# board_pa98.net
KiCad netlist of a schematic drawn in Altium Designer
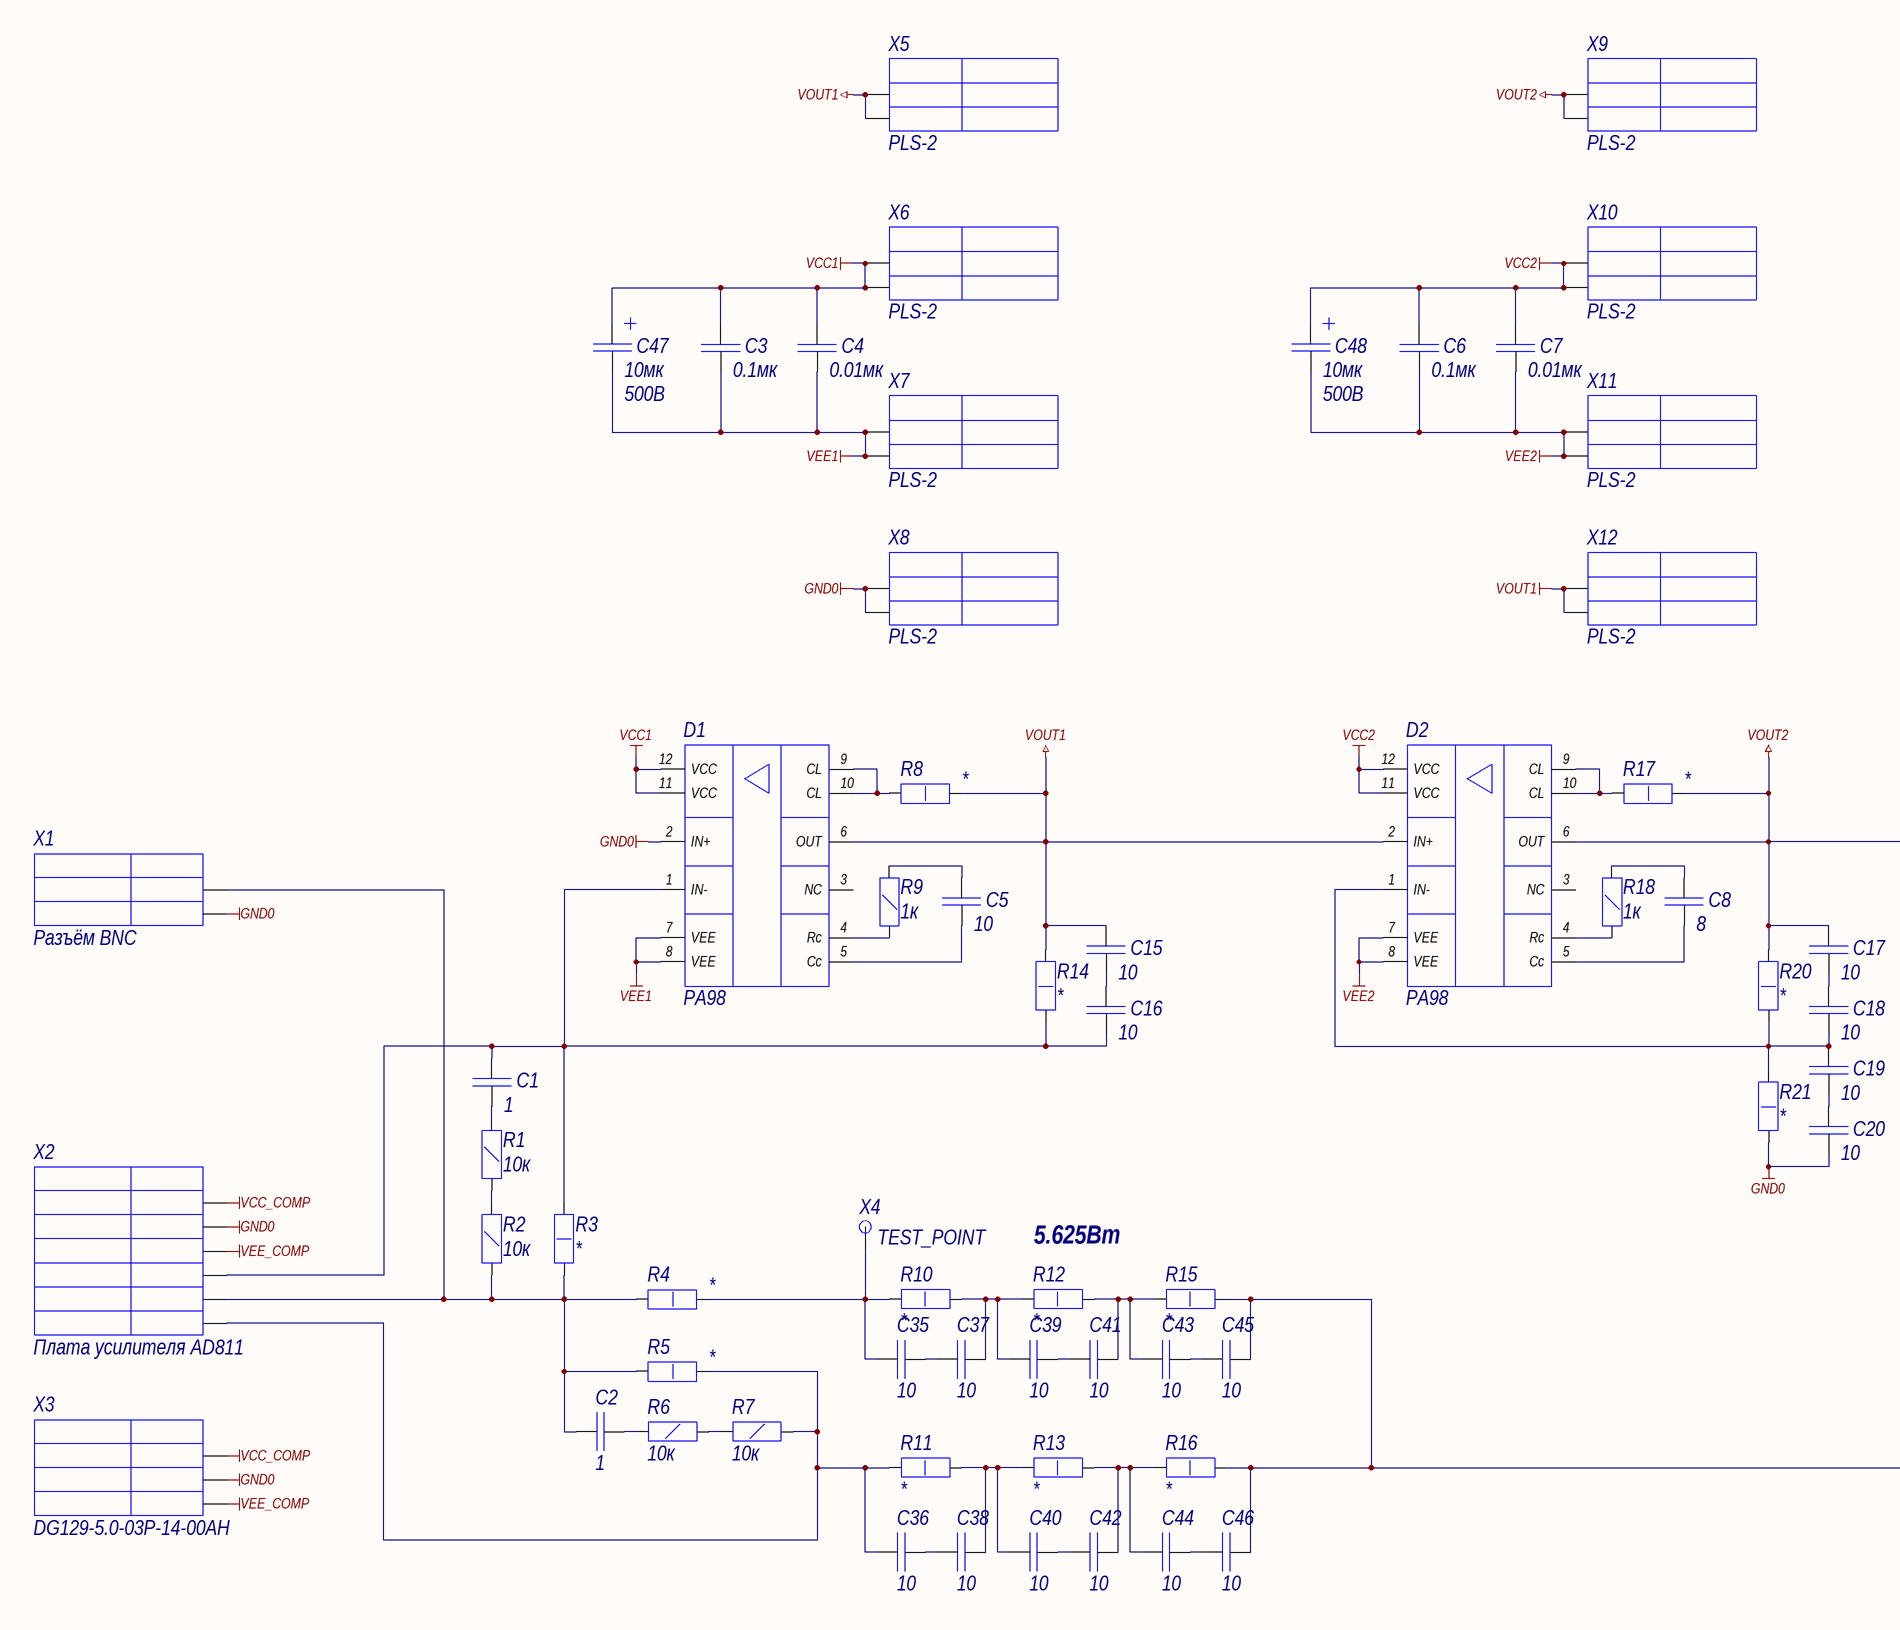
[diagram p0: board_pa98.SchDoc, left]
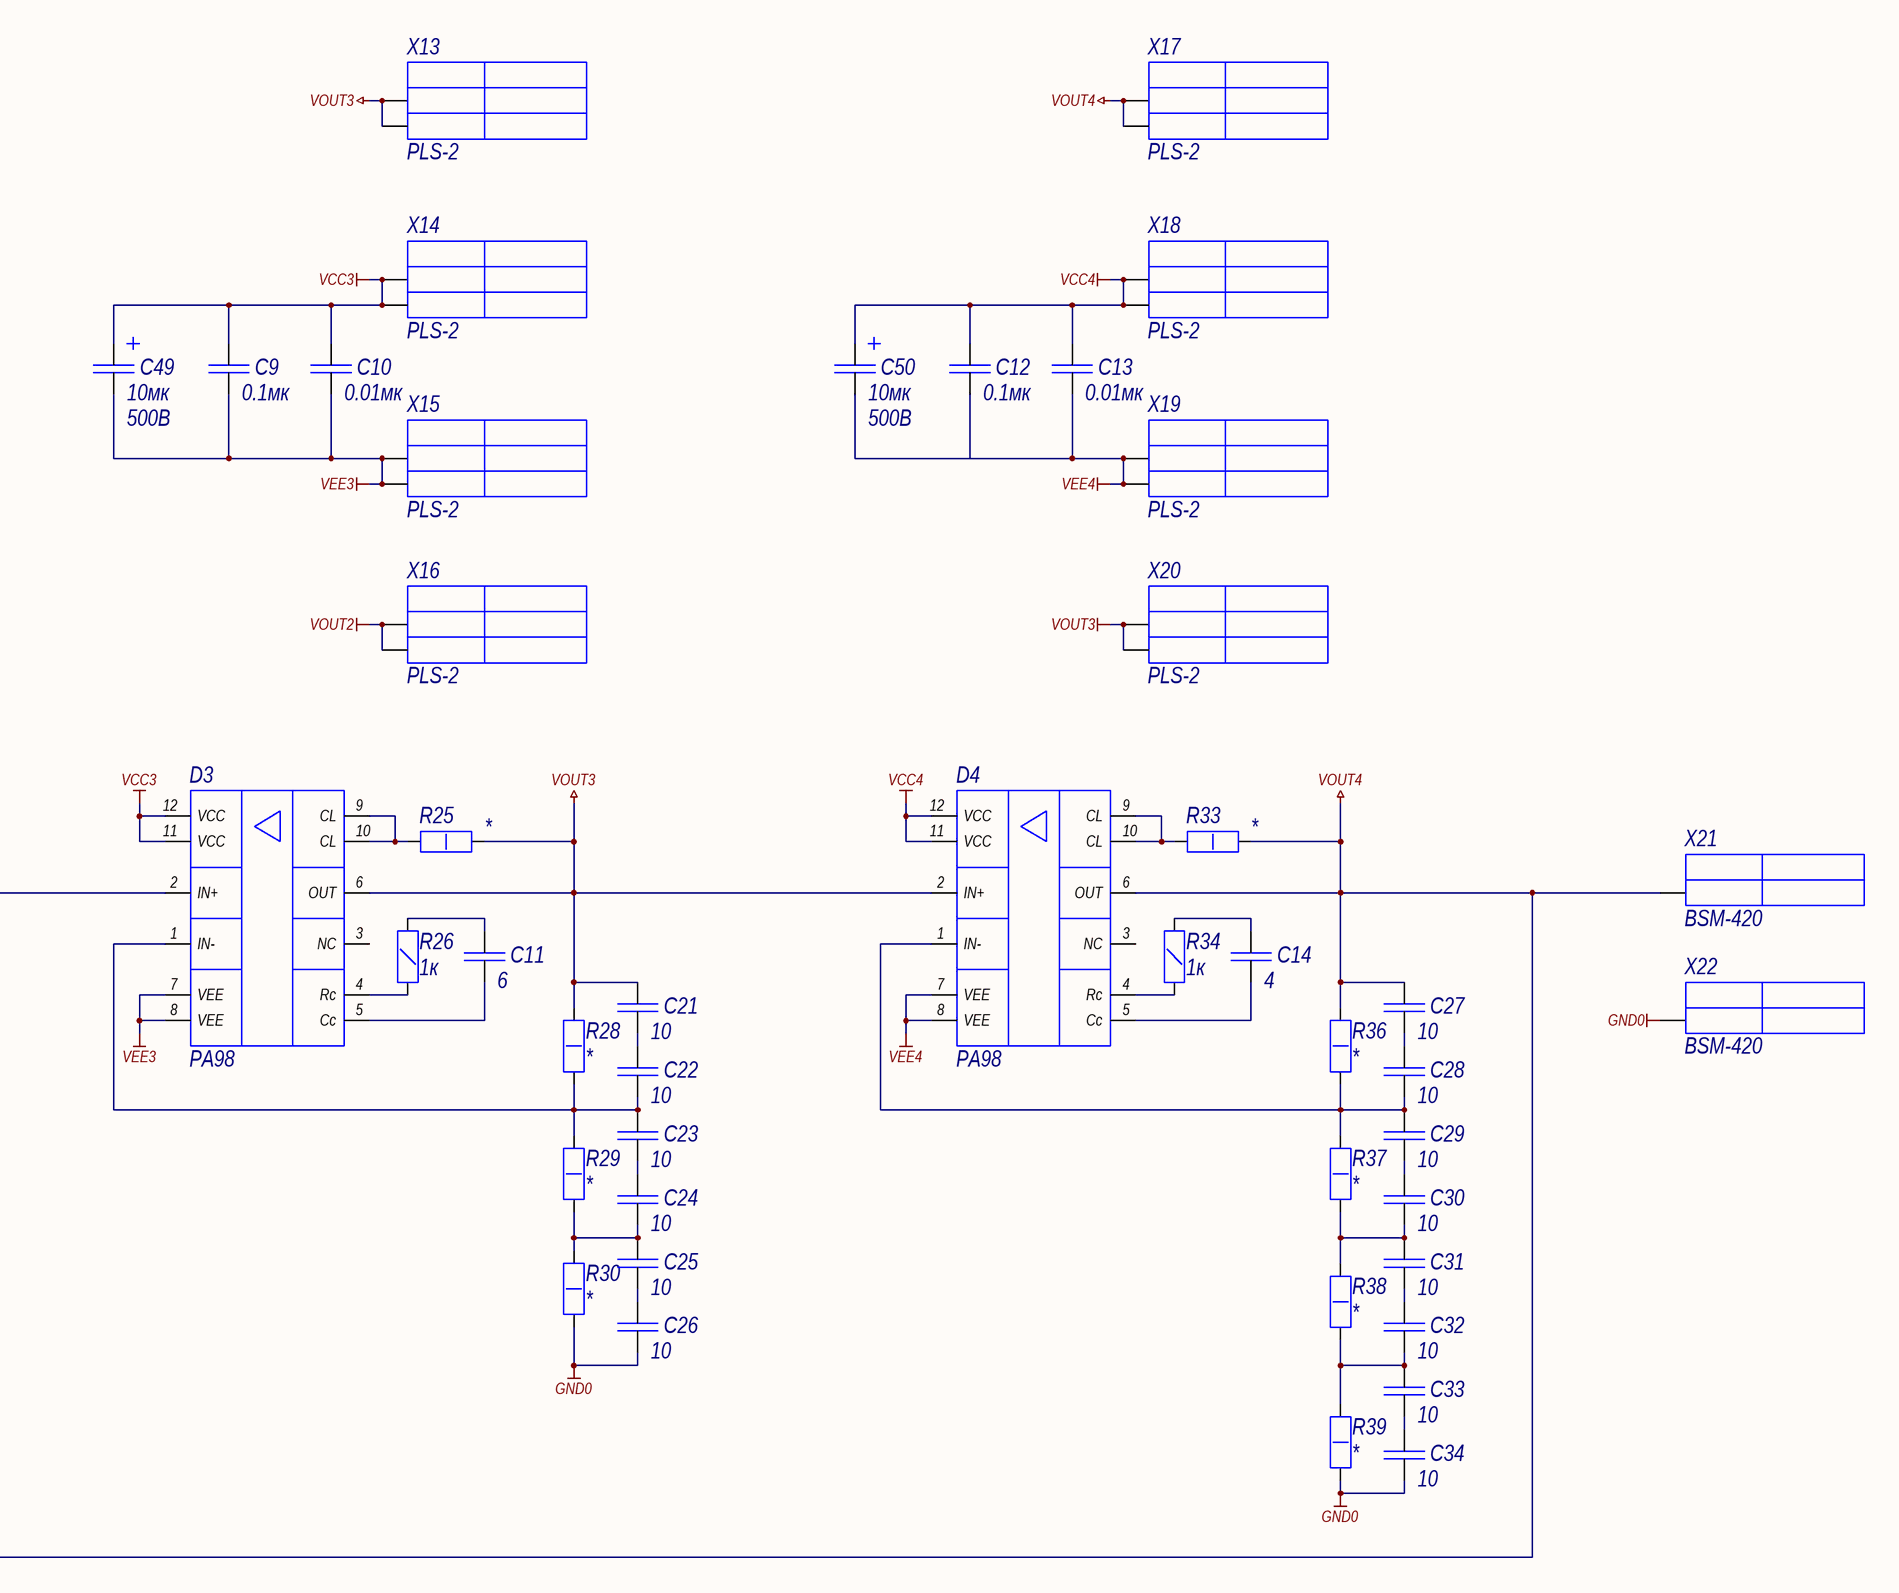
[diagram p1: board_pa98.SchDoc, right]

(export (version "E")
  (design (tool "Eeschema 10.0.6"))
  (components
    (comp (ref "C1")
      (value "1")
      (footprint "C-1206")
      (fields (field (name "VOLTAGE") "630В"))
      (libsource (lib "Capacitor") (part "C1206"))
    )
    (comp (ref "C2")
      (value "1")
      (footprint "C-1206")
      (fields (field (name "VOLTAGE") "630В"))
      (libsource (lib "Capacitor") (part "C1206"))
    )
    (comp (ref "C3")
      (value "0.1мк")
      (footprint "C-1812")
      (fields (field (name "VOLTAGE") "630"))
      (libsource (lib "Capacitor") (part "C1812"))
    )
    (comp (ref "C4")
      (value "0.01мк")
      (footprint "C-1206")
      (fields (field (name "VOLTAGE") "630"))
      (libsource (lib "Capacitor") (part "C1206"))
    )
    (comp (ref "C5")
      (value "10")
      (footprint "C-1206")
      (fields (field (name "VOLTAGE") "630В"))
      (libsource (lib "Capacitor") (part "C1206"))
    )
    (comp (ref "C6")
      (value "0.1мк")
      (footprint "C-1812")
      (fields (field (name "VOLTAGE") "630"))
      (libsource (lib "Capacitor") (part "C1812"))
    )
    (comp (ref "C7")
      (value "0.01мк")
      (footprint "C-1206")
      (fields (field (name "VOLTAGE") "630"))
      (libsource (lib "Capacitor") (part "C1206"))
    )
    (comp (ref "C8")
      (value "8")
      (footprint "C-1206")
      (fields (field (name "VOLTAGE") "630В"))
      (libsource (lib "Capacitor") (part "C1206"))
    )
    (comp (ref "C9")
      (value "0.1мк")
      (footprint "C-1812")
      (fields (field (name "VOLTAGE") "630"))
      (libsource (lib "Capacitor") (part "C1812"))
    )
    (comp (ref "C10")
      (value "0.01мк")
      (footprint "C-1206")
      (fields (field (name "VOLTAGE") "630"))
      (libsource (lib "Capacitor") (part "C1206"))
    )
    (comp (ref "C11")
      (value "6")
      (footprint "C-1206")
      (fields (field (name "VOLTAGE") "630В"))
      (libsource (lib "Capacitor") (part "C1206"))
    )
    (comp (ref "C12")
      (value "0.1мк")
      (footprint "C-1812")
      (fields (field (name "VOLTAGE") "630"))
      (libsource (lib "Capacitor") (part "C1812"))
    )
    (comp (ref "C13")
      (value "0.01мк")
      (footprint "C-1206")
      (fields (field (name "VOLTAGE") "630"))
      (libsource (lib "Capacitor") (part "C1206"))
    )
    (comp (ref "C14")
      (value "4")
      (footprint "C-1206")
      (fields (field (name "VOLTAGE") "630В"))
      (libsource (lib "Capacitor") (part "C1206"))
    )
    (comp (ref "C15")
      (value "10")
      (footprint "C-1206")
      (fields (field (name "VOLTAGE") "630В"))
      (libsource (lib "Capacitor") (part "C1206"))
    )
    (comp (ref "C16")
      (value "10")
      (footprint "C-1206")
      (fields (field (name "VOLTAGE") "630В"))
      (libsource (lib "Capacitor") (part "C1206"))
    )
    (comp (ref "C17")
      (value "10")
      (footprint "C-1206")
      (fields (field (name "VOLTAGE") "630В"))
      (libsource (lib "Capacitor") (part "C1206"))
    )
    (comp (ref "C18")
      (value "10")
      (footprint "C-1206")
      (fields (field (name "VOLTAGE") "630В"))
      (libsource (lib "Capacitor") (part "C1206"))
    )
    (comp (ref "C19")
      (value "10")
      (footprint "C-1206")
      (fields (field (name "VOLTAGE") "630В"))
      (libsource (lib "Capacitor") (part "C1206"))
    )
    (comp (ref "C20")
      (value "10")
      (footprint "C-1206")
      (fields (field (name "VOLTAGE") "630В"))
      (libsource (lib "Capacitor") (part "C1206"))
    )
    (comp (ref "C21")
      (value "10")
      (footprint "C-1206")
      (fields (field (name "VOLTAGE") "630В"))
      (libsource (lib "Capacitor") (part "C1206"))
    )
    (comp (ref "C22")
      (value "10")
      (footprint "C-1206")
      (fields (field (name "VOLTAGE") "630В"))
      (libsource (lib "Capacitor") (part "C1206"))
    )
    (comp (ref "C23")
      (value "10")
      (footprint "C-1206")
      (fields (field (name "VOLTAGE") "630В"))
      (libsource (lib "Capacitor") (part "C1206"))
    )
    (comp (ref "C24")
      (value "10")
      (footprint "C-1206")
      (fields (field (name "VOLTAGE") "630В"))
      (libsource (lib "Capacitor") (part "C1206"))
    )
    (comp (ref "C25")
      (value "10")
      (footprint "C-1206")
      (fields (field (name "VOLTAGE") "630В"))
      (libsource (lib "Capacitor") (part "C1206"))
    )
    (comp (ref "C26")
      (value "10")
      (footprint "C-1206")
      (fields (field (name "VOLTAGE") "630В"))
      (libsource (lib "Capacitor") (part "C1206"))
    )
    (comp (ref "C27")
      (value "10")
      (footprint "C-1206")
      (fields (field (name "VOLTAGE") "630В"))
      (libsource (lib "Capacitor") (part "C1206"))
    )
    (comp (ref "C28")
      (value "10")
      (footprint "C-1206")
      (fields (field (name "VOLTAGE") "630В"))
      (libsource (lib "Capacitor") (part "C1206"))
    )
    (comp (ref "C29")
      (value "10")
      (footprint "C-1206")
      (fields (field (name "VOLTAGE") "630В"))
      (libsource (lib "Capacitor") (part "C1206"))
    )
    (comp (ref "C30")
      (value "10")
      (footprint "C-1206")
      (fields (field (name "VOLTAGE") "630В"))
      (libsource (lib "Capacitor") (part "C1206"))
    )
    (comp (ref "C31")
      (value "10")
      (footprint "C-1206")
      (fields (field (name "VOLTAGE") "630В"))
      (libsource (lib "Capacitor") (part "C1206"))
    )
    (comp (ref "C32")
      (value "10")
      (footprint "C-1206")
      (fields (field (name "VOLTAGE") "630В"))
      (libsource (lib "Capacitor") (part "C1206"))
    )
    (comp (ref "C33")
      (value "10")
      (footprint "C-1206")
      (fields (field (name "VOLTAGE") "630В"))
      (libsource (lib "Capacitor") (part "C1206"))
    )
    (comp (ref "C34")
      (value "10")
      (footprint "C-1206")
      (fields (field (name "VOLTAGE") "630В"))
      (libsource (lib "Capacitor") (part "C1206"))
    )
    (comp (ref "C35")
      (value "10")
      (footprint "C-1206")
      (fields (field (name "VOLTAGE") "630В"))
      (libsource (lib "Capacitor") (part "C1206"))
    )
    (comp (ref "C36")
      (value "10")
      (footprint "C-1206")
      (fields (field (name "VOLTAGE") "630В"))
      (libsource (lib "Capacitor") (part "C1206"))
    )
    (comp (ref "C37")
      (value "10")
      (footprint "C-1206")
      (fields (field (name "VOLTAGE") "630В"))
      (libsource (lib "Capacitor") (part "C1206"))
    )
    (comp (ref "C38")
      (value "10")
      (footprint "C-1206")
      (fields (field (name "VOLTAGE") "630В"))
      (libsource (lib "Capacitor") (part "C1206"))
    )
    (comp (ref "C39")
      (value "10")
      (footprint "C-1206")
      (fields (field (name "VOLTAGE") "630В"))
      (libsource (lib "Capacitor") (part "C1206"))
    )
    (comp (ref "C40")
      (value "10")
      (footprint "C-1206")
      (fields (field (name "VOLTAGE") "630В"))
      (libsource (lib "Capacitor") (part "C1206"))
    )
    (comp (ref "C41")
      (value "10")
      (footprint "C-1206")
      (fields (field (name "VOLTAGE") "630В"))
      (libsource (lib "Capacitor") (part "C1206"))
    )
    (comp (ref "C42")
      (value "10")
      (footprint "C-1206")
      (fields (field (name "VOLTAGE") "630В"))
      (libsource (lib "Capacitor") (part "C1206"))
    )
    (comp (ref "C43")
      (value "10")
      (footprint "C-1206")
      (fields (field (name "VOLTAGE") "630В"))
      (libsource (lib "Capacitor") (part "C1206"))
    )
    (comp (ref "C44")
      (value "10")
      (footprint "C-1206")
      (fields (field (name "VOLTAGE") "630В"))
      (libsource (lib "Capacitor") (part "C1206"))
    )
    (comp (ref "C45")
      (value "10")
      (footprint "C-1206")
      (fields (field (name "VOLTAGE") "630В"))
      (libsource (lib "Capacitor") (part "C1206"))
    )
    (comp (ref "C46")
      (value "10")
      (footprint "C-1206")
      (fields (field (name "VOLTAGE") "630В"))
      (libsource (lib "Capacitor") (part "C1206"))
    )
    (comp (ref "C47")
      (value "10мк")
      (footprint "CAP: D13C5H25")
      (description "Конденсатор электролитический")
      (fields (field (name "VOLTAGE") "500В"))
      (libsource (lib "Capacitor") (part "Aluminum electrolytic capacitor"))
    )
    (comp (ref "C48")
      (value "10мк")
      (footprint "CAP: D13C5H25")
      (description "Конденсатор электролитический")
      (fields (field (name "VOLTAGE") "500В"))
      (libsource (lib "Capacitor") (part "Aluminum electrolytic capacitor"))
    )
    (comp (ref "C49")
      (value "10мк")
      (footprint "CAP: D13C5H25")
      (description "Конденсатор электролитический")
      (fields (field (name "VOLTAGE") "500В"))
      (libsource (lib "Capacitor") (part "Aluminum electrolytic capacitor"))
    )
    (comp (ref "C50")
      (value "10мк")
      (footprint "CAP: D13C5H25")
      (description "Конденсатор электролитический")
      (fields (field (name "VOLTAGE") "500В"))
      (libsource (lib "Capacitor") (part "Aluminum electrolytic capacitor"))
    )
    (comp (ref "D1")
      (value "PA98")
      (footprint "PA-98")
      (description "Микросхема  ОУ")
      (libsource (lib "IC_Operational_amp") (part "PA98"))
    )
    (comp (ref "D2")
      (value "PA98")
      (footprint "PA-98")
      (description "Микросхема  ОУ")
      (libsource (lib "IC_Operational_amp") (part "PA98"))
    )
    (comp (ref "D3")
      (value "PA98")
      (footprint "PA-98")
      (description "Микросхема  ОУ")
      (libsource (lib "IC_Operational_amp") (part "PA98"))
    )
    (comp (ref "D4")
      (value "PA98")
      (footprint "PA-98")
      (description "Микросхема  ОУ")
      (libsource (lib "IC_Operational_amp") (part "PA98"))
    )
    (comp (ref "R1")
      (value "10к")
      (footprint "R-1206")
      (description "Резистор SMD")
      (fields (field (name "TOLERANCE") "5%"))
      (libsource (lib "Resistor") (part "R1206"))
    )
    (comp (ref "R2")
      (value "10к")
      (footprint "R-1206")
      (description "Резистор SMD")
      (fields (field (name "TOLERANCE") "5%"))
      (libsource (lib "Resistor") (part "R1206"))
    )
    (comp (ref "R3")
      (value "*")
      (footprint "R-2512")
      (description "Резистор SMD")
      (fields (field (name "TOLERANCE") "5%"))
      (libsource (lib "Resistor") (part "R2512"))
    )
    (comp (ref "R4")
      (value "*")
      (footprint "R-2512")
      (description "Резистор SMD")
      (fields (field (name "TOLERANCE") "5%"))
      (libsource (lib "Resistor") (part "R2512"))
    )
    (comp (ref "R5")
      (value "*")
      (footprint "R-2512")
      (description "Резистор SMD")
      (fields (field (name "TOLERANCE") "5%"))
      (libsource (lib "Resistor") (part "R2512"))
    )
    (comp (ref "R6")
      (value "10к")
      (footprint "R-1206")
      (description "Резистор SMD")
      (fields (field (name "TOLERANCE") "5%"))
      (libsource (lib "Resistor") (part "R1206"))
    )
    (comp (ref "R7")
      (value "10к")
      (footprint "R-1206")
      (description "Резистор SMD")
      (fields (field (name "TOLERANCE") "5%"))
      (libsource (lib "Resistor") (part "R1206"))
    )
    (comp (ref "R8")
      (value "*")
      (footprint "R-2512")
      (description "Резистор SMD")
      (fields (field (name "TOLERANCE") "5%"))
      (libsource (lib "Resistor") (part "R2512"))
    )
    (comp (ref "R9")
      (value "1к")
      (footprint "R-1206")
      (description "Резистор SMD")
      (fields (field (name "TOLERANCE") "5%"))
      (libsource (lib "Resistor") (part "R1206"))
    )
    (comp (ref "R10")
      (value "*")
      (footprint "R-2512")
      (description "Резистор SMD")
      (fields (field (name "TOLERANCE") "5%"))
      (libsource (lib "Resistor") (part "R2512"))
    )
    (comp (ref "R11")
      (value "*")
      (footprint "R-2512")
      (description "Резистор SMD")
      (fields (field (name "TOLERANCE") "5%"))
      (libsource (lib "Resistor") (part "R2512"))
    )
    (comp (ref "R12")
      (value "*")
      (footprint "R-2512")
      (description "Резистор SMD")
      (fields (field (name "TOLERANCE") "5%"))
      (libsource (lib "Resistor") (part "R2512"))
    )
    (comp (ref "R13")
      (value "*")
      (footprint "R-2512")
      (description "Резистор SMD")
      (fields (field (name "TOLERANCE") "5%"))
      (libsource (lib "Resistor") (part "R2512"))
    )
    (comp (ref "R14")
      (value "*")
      (footprint "R-2512")
      (description "Резистор SMD")
      (fields (field (name "TOLERANCE") "5%"))
      (libsource (lib "Resistor") (part "R2512"))
    )
    (comp (ref "R15")
      (value "*")
      (footprint "R-2512")
      (description "Резистор SMD")
      (fields (field (name "TOLERANCE") "5%"))
      (libsource (lib "Resistor") (part "R2512"))
    )
    (comp (ref "R16")
      (value "*")
      (footprint "R-2512")
      (description "Резистор SMD")
      (fields (field (name "TOLERANCE") "5%"))
      (libsource (lib "Resistor") (part "R2512"))
    )
    (comp (ref "R17")
      (value "*")
      (footprint "R-2512")
      (description "Резистор SMD")
      (fields (field (name "TOLERANCE") "5%"))
      (libsource (lib "Resistor") (part "R2512"))
    )
    (comp (ref "R18")
      (value "1к")
      (footprint "R-1206")
      (description "Резистор SMD")
      (fields (field (name "TOLERANCE") "5%"))
      (libsource (lib "Resistor") (part "R1206"))
    )
    (comp (ref "R20")
      (value "*")
      (footprint "R-2512")
      (description "Резистор SMD")
      (fields (field (name "TOLERANCE") "5%"))
      (libsource (lib "Resistor") (part "R2512"))
    )
    (comp (ref "R21")
      (value "*")
      (footprint "R-2512")
      (description "Резистор SMD")
      (fields (field (name "TOLERANCE") "5%"))
      (libsource (lib "Resistor") (part "R2512"))
    )
    (comp (ref "R25")
      (value "*")
      (footprint "R-2512")
      (description "Резистор SMD")
      (fields (field (name "TOLERANCE") "5%"))
      (libsource (lib "Resistor") (part "R2512"))
    )
    (comp (ref "R26")
      (value "1к")
      (footprint "R-1206")
      (description "Резистор SMD")
      (fields (field (name "TOLERANCE") "5%"))
      (libsource (lib "Resistor") (part "R1206"))
    )
    (comp (ref "R28")
      (value "*")
      (footprint "R-2512")
      (description "Резистор SMD")
      (fields (field (name "TOLERANCE") "5%"))
      (libsource (lib "Resistor") (part "R2512"))
    )
    (comp (ref "R29")
      (value "*")
      (footprint "R-2512")
      (description "Резистор SMD")
      (fields (field (name "TOLERANCE") "5%"))
      (libsource (lib "Resistor") (part "R2512"))
    )
    (comp (ref "R30")
      (value "*")
      (footprint "R-2512")
      (description "Резистор SMD")
      (fields (field (name "TOLERANCE") "5%"))
      (libsource (lib "Resistor") (part "R2512"))
    )
    (comp (ref "R33")
      (value "*")
      (footprint "R-2512")
      (description "Резистор SMD")
      (fields (field (name "TOLERANCE") "5%"))
      (libsource (lib "Resistor") (part "R2512"))
    )
    (comp (ref "R34")
      (value "1к")
      (footprint "R-1206")
      (description "Резистор SMD")
      (fields (field (name "TOLERANCE") "5%"))
      (libsource (lib "Resistor") (part "R1206"))
    )
    (comp (ref "R36")
      (value "*")
      (footprint "R-2512")
      (description "Резистор SMD")
      (fields (field (name "TOLERANCE") "5%"))
      (libsource (lib "Resistor") (part "R2512"))
    )
    (comp (ref "R37")
      (value "*")
      (footprint "R-2512")
      (description "Резистор SMD")
      (fields (field (name "TOLERANCE") "5%"))
      (libsource (lib "Resistor") (part "R2512"))
    )
    (comp (ref "R38")
      (value "*")
      (footprint "R-2512")
      (description "Резистор SMD")
      (fields (field (name "TOLERANCE") "5%"))
      (libsource (lib "Resistor") (part "R2512"))
    )
    (comp (ref "R39")
      (value "*")
      (footprint "R-2512")
      (description "Резистор SMD")
      (fields (field (name "TOLERANCE") "5%"))
      (libsource (lib "Resistor") (part "R2512"))
    )
    (comp (ref "X1")
      (value "Разъём BNC")
      (footprint "BNC")
      (description "Разъём")
      (fields (field (name "PARTNUMBER") "32K249-400L5"))
      (libsource (lib "CONNECTORS") (part "BNC"))
    )
    (comp (ref "X2")
      (value "Плата усилителя AD811")
      (footprint "BOARD_AD811")
      (libsource (lib "BOARDS") (part "BOARD_AD811"))
    )
    (comp (ref "X3")
      (value "DG129-5.0-03P-14-00AH")
      (footprint "DG129-5.0-03P-14-00AH")
      (description "Разъем винтовой")
      (libsource (lib "CONNECTORS") (part "DG129-5.0-03P-14-00AH"))
    )
    (comp (ref "X4")
      (value "TEST_POINT")
      (footprint "TEST_POINT")
      (description "Тестовый контакт")
      (libsource (lib "CONNECTORS") (part "TEST_POINT"))
    )
    (comp (ref "X5")
      (value "PLS-2")
      (footprint "PLS-2")
      (description "Разъём штыревой")
      (libsource (lib "CONNECTORS") (part "PLS-2"))
    )
    (comp (ref "X6")
      (value "PLS-2")
      (footprint "PLS-2")
      (description "Разъём штыревой")
      (libsource (lib "CONNECTORS") (part "PLS-2"))
    )
    (comp (ref "X7")
      (value "PLS-2")
      (footprint "PLS-2")
      (description "Разъём штыревой")
      (libsource (lib "CONNECTORS") (part "PLS-2"))
    )
    (comp (ref "X8")
      (value "PLS-2")
      (footprint "PLS-2")
      (description "Разъём штыревой")
      (libsource (lib "CONNECTORS") (part "PLS-2"))
    )
    (comp (ref "X9")
      (value "PLS-2")
      (footprint "PLS-2")
      (description "Разъём штыревой")
      (libsource (lib "CONNECTORS") (part "PLS-2"))
    )
    (comp (ref "X10")
      (value "PLS-2")
      (footprint "PLS-2")
      (description "Разъём штыревой")
      (libsource (lib "CONNECTORS") (part "PLS-2"))
    )
    (comp (ref "X11")
      (value "PLS-2")
      (footprint "PLS-2")
      (description "Разъём штыревой")
      (libsource (lib "CONNECTORS") (part "PLS-2"))
    )
    (comp (ref "X12")
      (value "PLS-2")
      (footprint "PLS-2")
      (description "Разъём штыревой")
      (libsource (lib "CONNECTORS") (part "PLS-2"))
    )
    (comp (ref "X13")
      (value "PLS-2")
      (footprint "PLS-2")
      (description "Разъём штыревой")
      (libsource (lib "CONNECTORS") (part "PLS-2"))
    )
    (comp (ref "X14")
      (value "PLS-2")
      (footprint "PLS-2")
      (description "Разъём штыревой")
      (libsource (lib "CONNECTORS") (part "PLS-2"))
    )
    (comp (ref "X15")
      (value "PLS-2")
      (footprint "PLS-2")
      (description "Разъём штыревой")
      (libsource (lib "CONNECTORS") (part "PLS-2"))
    )
    (comp (ref "X16")
      (value "PLS-2")
      (footprint "PLS-2")
      (description "Разъём штыревой")
      (libsource (lib "CONNECTORS") (part "PLS-2"))
    )
    (comp (ref "X17")
      (value "PLS-2")
      (footprint "PLS-2")
      (description "Разъём штыревой")
      (libsource (lib "CONNECTORS") (part "PLS-2"))
    )
    (comp (ref "X18")
      (value "PLS-2")
      (footprint "PLS-2")
      (description "Разъём штыревой")
      (libsource (lib "CONNECTORS") (part "PLS-2"))
    )
    (comp (ref "X19")
      (value "PLS-2")
      (footprint "PLS-2")
      (description "Разъём штыревой")
      (libsource (lib "CONNECTORS") (part "PLS-2"))
    )
    (comp (ref "X20")
      (value "PLS-2")
      (footprint "PLS-2")
      (description "Разъём штыревой")
      (libsource (lib "CONNECTORS") (part "PLS-2"))
    )
    (comp (ref "X21")
      (value "BSM-420")
      (footprint "BSM-420-R")
      (description "Разъём")
      (fields (field (name "PARTNUMBER") "32K249-400L5"))
      (libsource (lib "CONNECTORS") (part "BSM-420"))
    )
    (comp (ref "X22")
      (value "BSM-420")
      (footprint "BSM-420-B")
      (description "Разъём")
      (fields (field (name "PARTNUMBER") "32K249-400L5"))
      (libsource (lib "CONNECTORS") (part "BSM-420"))
    )
  )
  (nets
    (net (code "1") (name "GND0") (class "Default")
      (node (ref "C20") (pin "2") (pintype "passive"))
      (node (ref "C26") (pin "2") (pintype "passive"))
      (node (ref "C34") (pin "2") (pintype "passive"))
      (node (ref "D1") (pin "2") (pinfunction "IN+_2") (pintype "passive"))
      (node (ref "R21") (pin "1") (pintype "passive"))
      (node (ref "R30") (pin "1") (pintype "passive"))
      (node (ref "R39") (pin "1") (pintype "passive"))
      (node (ref "X1") (pin "2") (pintype "passive"))
      (node (ref "X2") (pin "2") (pintype "passive"))
      (node (ref "X22") (pin "1") (pintype "passive"))
      (node (ref "X3") (pin "2") (pintype "passive"))
      (node (ref "X8") (pin "1") (pintype "passive"))
      (node (ref "X8") (pin "2") (pintype "passive"))
    )
    (net (code "2") (name "Net-(C1-Pad2)") (class "Default")
      (node (ref "C1") (pin "2") (pintype "passive"))
      (node (ref "R1") (pin "2") (pintype "passive"))
    )
    (net (code "3") (name "Net-(C2-Pad1)") (class "Default")
      (node (ref "C2") (pin "1") (pintype "passive"))
      (node (ref "R2") (pin "1") (pintype "passive"))
      (node (ref "R3") (pin "1") (pintype "passive"))
      (node (ref "R4") (pin "1") (pintype "passive"))
      (node (ref "R5") (pin "1") (pintype "passive"))
      (node (ref "X1") (pin "1") (pintype "passive"))
      (node (ref "X2") (pin "5") (pintype "passive"))
    )
    (net (code "4") (name "Net-(C2-Pad2)") (class "Default")
      (node (ref "C2") (pin "2") (pintype "passive"))
      (node (ref "R6") (pin "2") (pintype "passive"))
    )
    (net (code "5") (name "Net-(C5-Pad1)") (class "Default")
      (node (ref "C5") (pin "1") (pintype "passive"))
      (node (ref "R9") (pin "1") (pintype "passive"))
    )
    (net (code "6") (name "Net-(C8-Pad1)") (class "Default")
      (node (ref "C8") (pin "1") (pintype "passive"))
      (node (ref "R18") (pin "1") (pintype "passive"))
    )
    (net (code "7") (name "Net-(C11-Pad1)") (class "Default")
      (node (ref "C11") (pin "1") (pintype "passive"))
      (node (ref "R26") (pin "1") (pintype "passive"))
    )
    (net (code "8") (name "Net-(C14-Pad1)") (class "Default")
      (node (ref "C14") (pin "1") (pintype "passive"))
      (node (ref "R34") (pin "1") (pintype "passive"))
    )
    (net (code "9") (name "Net-(C15-Pad2)") (class "Default")
      (node (ref "C15") (pin "2") (pintype "passive"))
      (node (ref "C16") (pin "1") (pintype "passive"))
    )
    (net (code "10") (name "Net-(C17-Pad2)") (class "Default")
      (node (ref "C17") (pin "2") (pintype "passive"))
      (node (ref "C18") (pin "1") (pintype "passive"))
    )
    (net (code "11") (name "Net-(C19-Pad2)") (class "Default")
      (node (ref "C19") (pin "2") (pintype "passive"))
      (node (ref "C20") (pin "1") (pintype "passive"))
    )
    (net (code "12") (name "Net-(C21-Pad2)") (class "Default")
      (node (ref "C21") (pin "2") (pintype "passive"))
      (node (ref "C22") (pin "1") (pintype "passive"))
    )
    (net (code "13") (name "Net-(C23-Pad2)") (class "Default")
      (node (ref "C23") (pin "2") (pintype "passive"))
      (node (ref "C24") (pin "1") (pintype "passive"))
    )
    (net (code "14") (name "Net-(C24-Pad2)") (class "Default")
      (node (ref "C24") (pin "2") (pintype "passive"))
      (node (ref "C25") (pin "1") (pintype "passive"))
      (node (ref "R29") (pin "1") (pintype "passive"))
      (node (ref "R30") (pin "2") (pintype "passive"))
    )
    (net (code "15") (name "Net-(C25-Pad2)") (class "Default")
      (node (ref "C25") (pin "2") (pintype "passive"))
      (node (ref "C26") (pin "1") (pintype "passive"))
    )
    (net (code "16") (name "Net-(C27-Pad2)") (class "Default")
      (node (ref "C27") (pin "2") (pintype "passive"))
      (node (ref "C28") (pin "1") (pintype "passive"))
    )
    (net (code "17") (name "Net-(C29-Pad2)") (class "Default")
      (node (ref "C29") (pin "2") (pintype "passive"))
      (node (ref "C30") (pin "1") (pintype "passive"))
    )
    (net (code "18") (name "Net-(C30-Pad2)") (class "Default")
      (node (ref "C30") (pin "2") (pintype "passive"))
      (node (ref "C31") (pin "1") (pintype "passive"))
      (node (ref "R37") (pin "1") (pintype "passive"))
      (node (ref "R38") (pin "2") (pintype "passive"))
    )
    (net (code "19") (name "Net-(C31-Pad2)") (class "Default")
      (node (ref "C31") (pin "2") (pintype "passive"))
      (node (ref "C32") (pin "1") (pintype "passive"))
    )
    (net (code "20") (name "Net-(C32-Pad2)") (class "Default")
      (node (ref "C32") (pin "2") (pintype "passive"))
      (node (ref "C33") (pin "1") (pintype "passive"))
      (node (ref "R38") (pin "1") (pintype "passive"))
      (node (ref "R39") (pin "2") (pintype "passive"))
    )
    (net (code "21") (name "Net-(C33-Pad2)") (class "Default")
      (node (ref "C33") (pin "2") (pintype "passive"))
      (node (ref "C34") (pin "1") (pintype "passive"))
    )
    (net (code "22") (name "Net-(C35-Pad1)") (class "Default")
      (node (ref "C35") (pin "1") (pintype "passive"))
      (node (ref "C37") (pin "2") (pintype "passive"))
    )
    (net (code "23") (name "Net-(C35-Pad2)") (class "Default")
      (node (ref "C35") (pin "2") (pintype "passive"))
      (node (ref "R10") (pin "2") (pintype "passive"))
      (node (ref "R4") (pin "2") (pintype "passive"))
      (node (ref "X4") (pin "1") (pinfunction "1_1") (pintype "passive"))
    )
    (net (code "24") (name "Net-(C36-Pad1)") (class "Default")
      (node (ref "C36") (pin "1") (pintype "passive"))
      (node (ref "C38") (pin "2") (pintype "passive"))
    )
    (net (code "25") (name "Net-(C36-Pad2)") (class "Default")
      (node (ref "C36") (pin "2") (pintype "passive"))
      (node (ref "R11") (pin "2") (pintype "passive"))
      (node (ref "R5") (pin "2") (pintype "passive"))
      (node (ref "R7") (pin "1") (pintype "passive"))
      (node (ref "X2") (pin "6") (pintype "passive"))
    )
    (net (code "26") (name "Net-(C37-Pad1)") (class "Default")
      (node (ref "C37") (pin "1") (pintype "passive"))
      (node (ref "C39") (pin "2") (pintype "passive"))
      (node (ref "R10") (pin "1") (pintype "passive"))
      (node (ref "R12") (pin "2") (pintype "passive"))
    )
    (net (code "27") (name "Net-(C38-Pad1)") (class "Default")
      (node (ref "C38") (pin "1") (pintype "passive"))
      (node (ref "C40") (pin "2") (pintype "passive"))
      (node (ref "R11") (pin "1") (pintype "passive"))
      (node (ref "R13") (pin "2") (pintype "passive"))
    )
    (net (code "28") (name "Net-(C39-Pad1)") (class "Default")
      (node (ref "C39") (pin "1") (pintype "passive"))
      (node (ref "C41") (pin "2") (pintype "passive"))
    )
    (net (code "29") (name "Net-(C40-Pad1)") (class "Default")
      (node (ref "C40") (pin "1") (pintype "passive"))
      (node (ref "C42") (pin "2") (pintype "passive"))
    )
    (net (code "30") (name "Net-(C41-Pad1)") (class "Default")
      (node (ref "C41") (pin "1") (pintype "passive"))
      (node (ref "C43") (pin "2") (pintype "passive"))
      (node (ref "R12") (pin "1") (pintype "passive"))
      (node (ref "R15") (pin "2") (pintype "passive"))
    )
    (net (code "31") (name "Net-(C42-Pad1)") (class "Default")
      (node (ref "C42") (pin "1") (pintype "passive"))
      (node (ref "C44") (pin "2") (pintype "passive"))
      (node (ref "R13") (pin "1") (pintype "passive"))
      (node (ref "R16") (pin "2") (pintype "passive"))
    )
    (net (code "32") (name "Net-(C43-Pad1)") (class "Default")
      (node (ref "C43") (pin "1") (pintype "passive"))
      (node (ref "C45") (pin "2") (pintype "passive"))
    )
    (net (code "33") (name "Net-(C44-Pad1)") (class "Default")
      (node (ref "C44") (pin "1") (pintype "passive"))
      (node (ref "C46") (pin "2") (pintype "passive"))
    )
    (net (code "34") (name "Net-(D1-CL-Pad10)") (class "Default")
      (node (ref "D1") (pin "10") (pinfunction "CL_10") (pintype "passive"))
      (node (ref "D1") (pin "9") (pinfunction "CL_9") (pintype "passive"))
      (node (ref "R8") (pin "1") (pintype "passive"))
    )
    (net (code "35") (name "Net-(D1-Cc)") (class "Default")
      (node (ref "C5") (pin "2") (pintype "passive"))
      (node (ref "D1") (pin "5") (pinfunction "Cc_5") (pintype "passive"))
    )
    (net (code "36") (name "Net-(D1-IN-)") (class "Default")
      (node (ref "C1") (pin "1") (pintype "passive"))
      (node (ref "C16") (pin "2") (pintype "passive"))
      (node (ref "D1") (pin "1") (pinfunction "IN-_1") (pintype "passive"))
      (node (ref "R14") (pin "1") (pintype "passive"))
      (node (ref "R3") (pin "2") (pintype "passive"))
      (node (ref "X2") (pin "4") (pintype "passive"))
    )
    (net (code "37") (name "Net-(D1-Rc)") (class "Default")
      (node (ref "D1") (pin "4") (pinfunction "Rc_4") (pintype "passive"))
      (node (ref "R9") (pin "2") (pintype "passive"))
    )
    (net (code "38") (name "Net-(D2-CL-Pad10)") (class "Default")
      (node (ref "D2") (pin "10") (pinfunction "CL_10") (pintype "passive"))
      (node (ref "D2") (pin "9") (pinfunction "CL_9") (pintype "passive"))
      (node (ref "R17") (pin "1") (pintype "passive"))
    )
    (net (code "39") (name "Net-(D2-Cc)") (class "Default")
      (node (ref "C8") (pin "2") (pintype "passive"))
      (node (ref "D2") (pin "5") (pinfunction "Cc_5") (pintype "passive"))
    )
    (net (code "40") (name "Net-(D2-IN-)") (class "Default")
      (node (ref "C18") (pin "2") (pintype "passive"))
      (node (ref "C19") (pin "1") (pintype "passive"))
      (node (ref "D2") (pin "1") (pinfunction "IN-_1") (pintype "passive"))
      (node (ref "R20") (pin "1") (pintype "passive"))
      (node (ref "R21") (pin "2") (pintype "passive"))
    )
    (net (code "41") (name "Net-(D2-Rc)") (class "Default")
      (node (ref "D2") (pin "4") (pinfunction "Rc_4") (pintype "passive"))
      (node (ref "R18") (pin "2") (pintype "passive"))
    )
    (net (code "42") (name "Net-(D3-CL-Pad10)") (class "Default")
      (node (ref "D3") (pin "10") (pinfunction "CL_10") (pintype "passive"))
      (node (ref "D3") (pin "9") (pinfunction "CL_9") (pintype "passive"))
      (node (ref "R25") (pin "1") (pintype "passive"))
    )
    (net (code "43") (name "Net-(D3-Cc)") (class "Default")
      (node (ref "C11") (pin "2") (pintype "passive"))
      (node (ref "D3") (pin "5") (pinfunction "Cc_5") (pintype "passive"))
    )
    (net (code "44") (name "Net-(D3-IN-)") (class "Default")
      (node (ref "C22") (pin "2") (pintype "passive"))
      (node (ref "C23") (pin "1") (pintype "passive"))
      (node (ref "D3") (pin "1") (pinfunction "IN-_1") (pintype "passive"))
      (node (ref "R28") (pin "1") (pintype "passive"))
      (node (ref "R29") (pin "2") (pintype "passive"))
    )
    (net (code "45") (name "Net-(D3-Rc)") (class "Default")
      (node (ref "D3") (pin "4") (pinfunction "Rc_4") (pintype "passive"))
      (node (ref "R26") (pin "2") (pintype "passive"))
    )
    (net (code "46") (name "Net-(D4-CL-Pad10)") (class "Default")
      (node (ref "D4") (pin "10") (pinfunction "CL_10") (pintype "passive"))
      (node (ref "D4") (pin "9") (pinfunction "CL_9") (pintype "passive"))
      (node (ref "R33") (pin "1") (pintype "passive"))
    )
    (net (code "47") (name "Net-(D4-Cc)") (class "Default")
      (node (ref "C14") (pin "2") (pintype "passive"))
      (node (ref "D4") (pin "5") (pinfunction "Cc_5") (pintype "passive"))
    )
    (net (code "48") (name "Net-(D4-IN-)") (class "Default")
      (node (ref "C28") (pin "2") (pintype "passive"))
      (node (ref "C29") (pin "1") (pintype "passive"))
      (node (ref "D4") (pin "1") (pinfunction "IN-_1") (pintype "passive"))
      (node (ref "R36") (pin "1") (pintype "passive"))
      (node (ref "R37") (pin "2") (pintype "passive"))
    )
    (net (code "49") (name "Net-(D4-Rc)") (class "Default")
      (node (ref "D4") (pin "4") (pinfunction "Rc_4") (pintype "passive"))
      (node (ref "R34") (pin "2") (pintype "passive"))
    )
    (net (code "50") (name "Net-(R1-Pad1)") (class "Default")
      (node (ref "R1") (pin "1") (pintype "passive"))
      (node (ref "R2") (pin "2") (pintype "passive"))
    )
    (net (code "51") (name "Net-(R6-Pad1)") (class "Default")
      (node (ref "R6") (pin "1") (pintype "passive"))
      (node (ref "R7") (pin "2") (pintype "passive"))
    )
    (net (code "52") (name "VCC1") (class "Default")
      (node (ref "C3") (pin "2") (pintype "passive"))
      (node (ref "C4") (pin "2") (pintype "passive"))
      (node (ref "C47") (pin "1") (pintype "passive"))
      (node (ref "D1") (pin "11") (pinfunction "VCC_11") (pintype "passive"))
      (node (ref "D1") (pin "12") (pinfunction "VCC_12") (pintype "passive"))
      (node (ref "X6") (pin "1") (pintype "passive"))
      (node (ref "X6") (pin "2") (pintype "passive"))
    )
    (net (code "53") (name "VCC2") (class "Default")
      (node (ref "C48") (pin "1") (pintype "passive"))
      (node (ref "C6") (pin "2") (pintype "passive"))
      (node (ref "C7") (pin "2") (pintype "passive"))
      (node (ref "D2") (pin "11") (pinfunction "VCC_11") (pintype "passive"))
      (node (ref "D2") (pin "12") (pinfunction "VCC_12") (pintype "passive"))
      (node (ref "X10") (pin "1") (pintype "passive"))
      (node (ref "X10") (pin "2") (pintype "passive"))
    )
    (net (code "54") (name "VCC3") (class "Default")
      (node (ref "C10") (pin "2") (pintype "passive"))
      (node (ref "C49") (pin "1") (pintype "passive"))
      (node (ref "C9") (pin "2") (pintype "passive"))
      (node (ref "D3") (pin "11") (pinfunction "VCC_11") (pintype "passive"))
      (node (ref "D3") (pin "12") (pinfunction "VCC_12") (pintype "passive"))
      (node (ref "X14") (pin "1") (pintype "passive"))
      (node (ref "X14") (pin "2") (pintype "passive"))
    )
    (net (code "55") (name "VCC4") (class "Default")
      (node (ref "C12") (pin "2") (pintype "passive"))
      (node (ref "C13") (pin "2") (pintype "passive"))
      (node (ref "C50") (pin "1") (pintype "passive"))
      (node (ref "D4") (pin "11") (pinfunction "VCC_11") (pintype "passive"))
      (node (ref "D4") (pin "12") (pinfunction "VCC_12") (pintype "passive"))
      (node (ref "X18") (pin "1") (pintype "passive"))
      (node (ref "X18") (pin "2") (pintype "passive"))
    )
    (net (code "56") (name "VCC_COMP") (class "Default")
      (node (ref "X2") (pin "1") (pintype "passive"))
      (node (ref "X3") (pin "1") (pintype "passive"))
    )
    (net (code "57") (name "VEE1") (class "Default")
      (node (ref "C3") (pin "1") (pintype "passive"))
      (node (ref "C4") (pin "1") (pintype "passive"))
      (node (ref "C47") (pin "2") (pintype "passive"))
      (node (ref "D1") (pin "7") (pinfunction "VEE_7") (pintype "passive"))
      (node (ref "D1") (pin "8") (pinfunction "VEE_8") (pintype "passive"))
      (node (ref "X7") (pin "1") (pintype "passive"))
      (node (ref "X7") (pin "2") (pintype "passive"))
    )
    (net (code "58") (name "VEE2") (class "Default")
      (node (ref "C48") (pin "2") (pintype "passive"))
      (node (ref "C6") (pin "1") (pintype "passive"))
      (node (ref "C7") (pin "1") (pintype "passive"))
      (node (ref "D2") (pin "7") (pinfunction "VEE_7") (pintype "passive"))
      (node (ref "D2") (pin "8") (pinfunction "VEE_8") (pintype "passive"))
      (node (ref "X11") (pin "1") (pintype "passive"))
      (node (ref "X11") (pin "2") (pintype "passive"))
    )
    (net (code "59") (name "VEE3") (class "Default")
      (node (ref "C10") (pin "1") (pintype "passive"))
      (node (ref "C49") (pin "2") (pintype "passive"))
      (node (ref "C9") (pin "1") (pintype "passive"))
      (node (ref "D3") (pin "7") (pinfunction "VEE_7") (pintype "passive"))
      (node (ref "D3") (pin "8") (pinfunction "VEE_8") (pintype "passive"))
      (node (ref "X15") (pin "1") (pintype "passive"))
      (node (ref "X15") (pin "2") (pintype "passive"))
    )
    (net (code "60") (name "VEE4") (class "Default")
      (node (ref "C12") (pin "1") (pintype "passive"))
      (node (ref "C13") (pin "1") (pintype "passive"))
      (node (ref "C50") (pin "2") (pintype "passive"))
      (node (ref "D4") (pin "7") (pinfunction "VEE_7") (pintype "passive"))
      (node (ref "D4") (pin "8") (pinfunction "VEE_8") (pintype "passive"))
      (node (ref "X19") (pin "1") (pintype "passive"))
      (node (ref "X19") (pin "2") (pintype "passive"))
    )
    (net (code "61") (name "VEE_COMP") (class "Default")
      (node (ref "X2") (pin "3") (pintype "passive"))
      (node (ref "X3") (pin "3") (pintype "passive"))
    )
    (net (code "62") (name "VOUT1") (class "Default")
      (node (ref "C15") (pin "1") (pintype "passive"))
      (node (ref "D1") (pin "6") (pinfunction "OUT_6") (pintype "passive"))
      (node (ref "D2") (pin "2") (pinfunction "IN+_2") (pintype "passive"))
      (node (ref "R14") (pin "2") (pintype "passive"))
      (node (ref "R8") (pin "2") (pintype "passive"))
      (node (ref "X12") (pin "1") (pintype "passive"))
      (node (ref "X12") (pin "2") (pintype "passive"))
      (node (ref "X5") (pin "1") (pintype "passive"))
      (node (ref "X5") (pin "2") (pintype "passive"))
    )
    (net (code "63") (name "VOUT2") (class "Default")
      (node (ref "C17") (pin "1") (pintype "passive"))
      (node (ref "D2") (pin "6") (pinfunction "OUT_6") (pintype "passive"))
      (node (ref "D3") (pin "2") (pinfunction "IN+_2") (pintype "passive"))
      (node (ref "R17") (pin "2") (pintype "passive"))
      (node (ref "R20") (pin "2") (pintype "passive"))
      (node (ref "X16") (pin "1") (pintype "passive"))
      (node (ref "X16") (pin "2") (pintype "passive"))
      (node (ref "X9") (pin "1") (pintype "passive"))
      (node (ref "X9") (pin "2") (pintype "passive"))
    )
    (net (code "64") (name "VOUT3") (class "Default")
      (node (ref "C21") (pin "1") (pintype "passive"))
      (node (ref "D3") (pin "6") (pinfunction "OUT_6") (pintype "passive"))
      (node (ref "D4") (pin "2") (pinfunction "IN+_2") (pintype "passive"))
      (node (ref "R25") (pin "2") (pintype "passive"))
      (node (ref "R28") (pin "2") (pintype "passive"))
      (node (ref "X13") (pin "1") (pintype "passive"))
      (node (ref "X13") (pin "2") (pintype "passive"))
      (node (ref "X20") (pin "1") (pintype "passive"))
      (node (ref "X20") (pin "2") (pintype "passive"))
    )
    (net (code "65") (name "VOUT4") (class "Default")
      (node (ref "C27") (pin "1") (pintype "passive"))
      (node (ref "C45") (pin "1") (pintype "passive"))
      (node (ref "C46") (pin "1") (pintype "passive"))
      (node (ref "D4") (pin "6") (pinfunction "OUT_6") (pintype "passive"))
      (node (ref "R15") (pin "1") (pintype "passive"))
      (node (ref "R16") (pin "1") (pintype "passive"))
      (node (ref "R33") (pin "2") (pintype "passive"))
      (node (ref "R36") (pin "2") (pintype "passive"))
      (node (ref "X17") (pin "1") (pintype "passive"))
      (node (ref "X17") (pin "2") (pintype "passive"))
      (node (ref "X21") (pin "1") (pintype "passive"))
    )
    (net (code "66") (name "unconnected-(D1-NC-Pad3)") (class "Default")
      (node (ref "D1") (pin "3") (pinfunction "NC_3") (pintype "passive"))
    )
    (net (code "67") (name "unconnected-(D2-NC-Pad3)") (class "Default")
      (node (ref "D2") (pin "3") (pinfunction "NC_3") (pintype "passive"))
    )
    (net (code "68") (name "unconnected-(D3-NC-Pad3)") (class "Default")
      (node (ref "D3") (pin "3") (pinfunction "NC_3") (pintype "passive"))
    )
    (net (code "69") (name "unconnected-(D4-NC-Pad3)") (class "Default")
      (node (ref "D4") (pin "3") (pinfunction "NC_3") (pintype "passive"))
    )
  )
)
